# Power_LPS_ADJ.net
KiCad netlist of a schematic drawn in Altium Designer
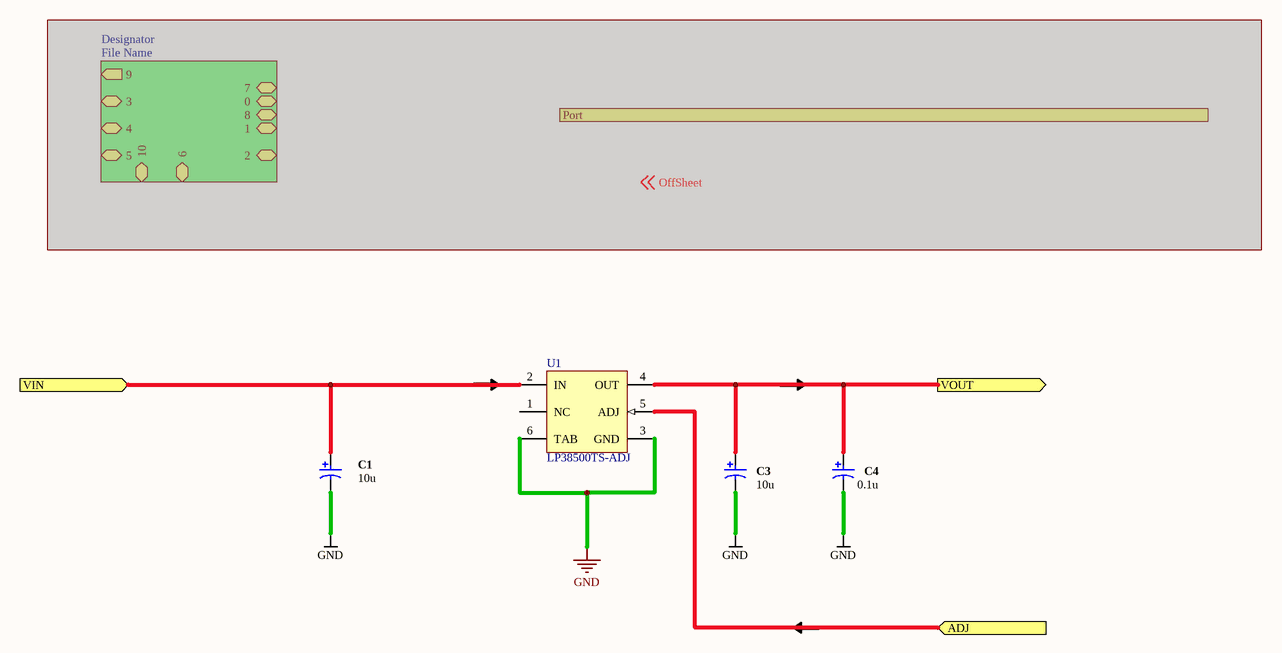
[diagram p0: Power_LPS_ADJ.SchDoc]

(export (version "E")
  (design (tool "Eeschema 10.0.6"))
  (components
    (comp (ref "C1")
      (value "10u")
      (footprint "CAPC3528-STAR")
      (description "Capacitor, Tantalum, 10uF 10% 20V MCCT-B (3528)")
      (fields (field (name "TOLERANCE") "10 %"))
      (libsource (lib "altium-import") (part "root_0_CAP-P_"))
    )
    (comp (ref "C3")
      (value "10u")
      (footprint "CAPC3528-STAR")
      (description "Capacitor, Tantalum, 10uF 10% 20V MCCT-B (3528)")
      (fields (field (name "TOLERANCE") "10 %"))
      (libsource (lib "altium-import") (part "root_0_CAP-P_"))
    )
    (comp (ref "C4")
      (value "0.1u")
      (footprint "CAPC7343-STAR")
      (description "Capacitor, Tantalum, 220uF 10% 10V MCCT-D (7343-31)")
      (fields (field (name "TOLERANCE") "10 %"))
      (libsource (lib "altium-import") (part "root_0_CAP-P_"))
    )
    (comp (ref "U1")
      (value "LP38500TS-ADJ")
      (footprint "TS5B_M")
      (description "1.5A FlexCap Low Dropout Linear Regulator for 2.7V to 5.5V Inputs, 5-pin TO-263")
      (fields (field (name "MANUFACTURER") "National Semiconductor"))
      (libsource (lib "National Semiconductor LDO") (part "LP38500TS-ADJ"))
    )
  )
  (nets
    (net (code "12") (name "/ADJ") (class "Default")
      (node (ref "U1") (pin "5") (pinfunction "ADJ_5") (pintype "input"))
    )
    (net (code "14") (name "/VIN") (class "Default")
      (node (ref "C1") (pin "1") (pinfunction "1_1") (pintype "passive"))
      (node (ref "U1") (pin "2") (pinfunction "IN_2") (pintype "power_in"))
    )
    (net (code "15") (name "/VOUT") (class "Default")
      (node (ref "C3") (pin "1") (pinfunction "1_1") (pintype "passive"))
      (node (ref "C4") (pin "1") (pinfunction "1_1") (pintype "passive"))
      (node (ref "U1") (pin "4") (pinfunction "OUT_4") (pintype "power_in"))
    )
    (net (code "16") (name "GND") (class "Default")
      (node (ref "C1") (pin "2") (pinfunction "2_2") (pintype "passive"))
      (node (ref "C3") (pin "2") (pinfunction "2_2") (pintype "passive"))
      (node (ref "C4") (pin "2") (pinfunction "2_2") (pintype "passive"))
      (node (ref "U1") (pin "3") (pinfunction "GND_3") (pintype "power_in"))
      (node (ref "U1") (pin "6") (pinfunction "TAB_6") (pintype "power_in"))
    )
    (net (code "18") (name "unconnected-(U1-NC-Pad1)") (class "Default")
      (node (ref "U1") (pin "1") (pinfunction "NC_1") (pintype "passive"))
    )
  )
)
